# 1_P1.net
KiCad netlist of a schematic drawn in Altium Designer
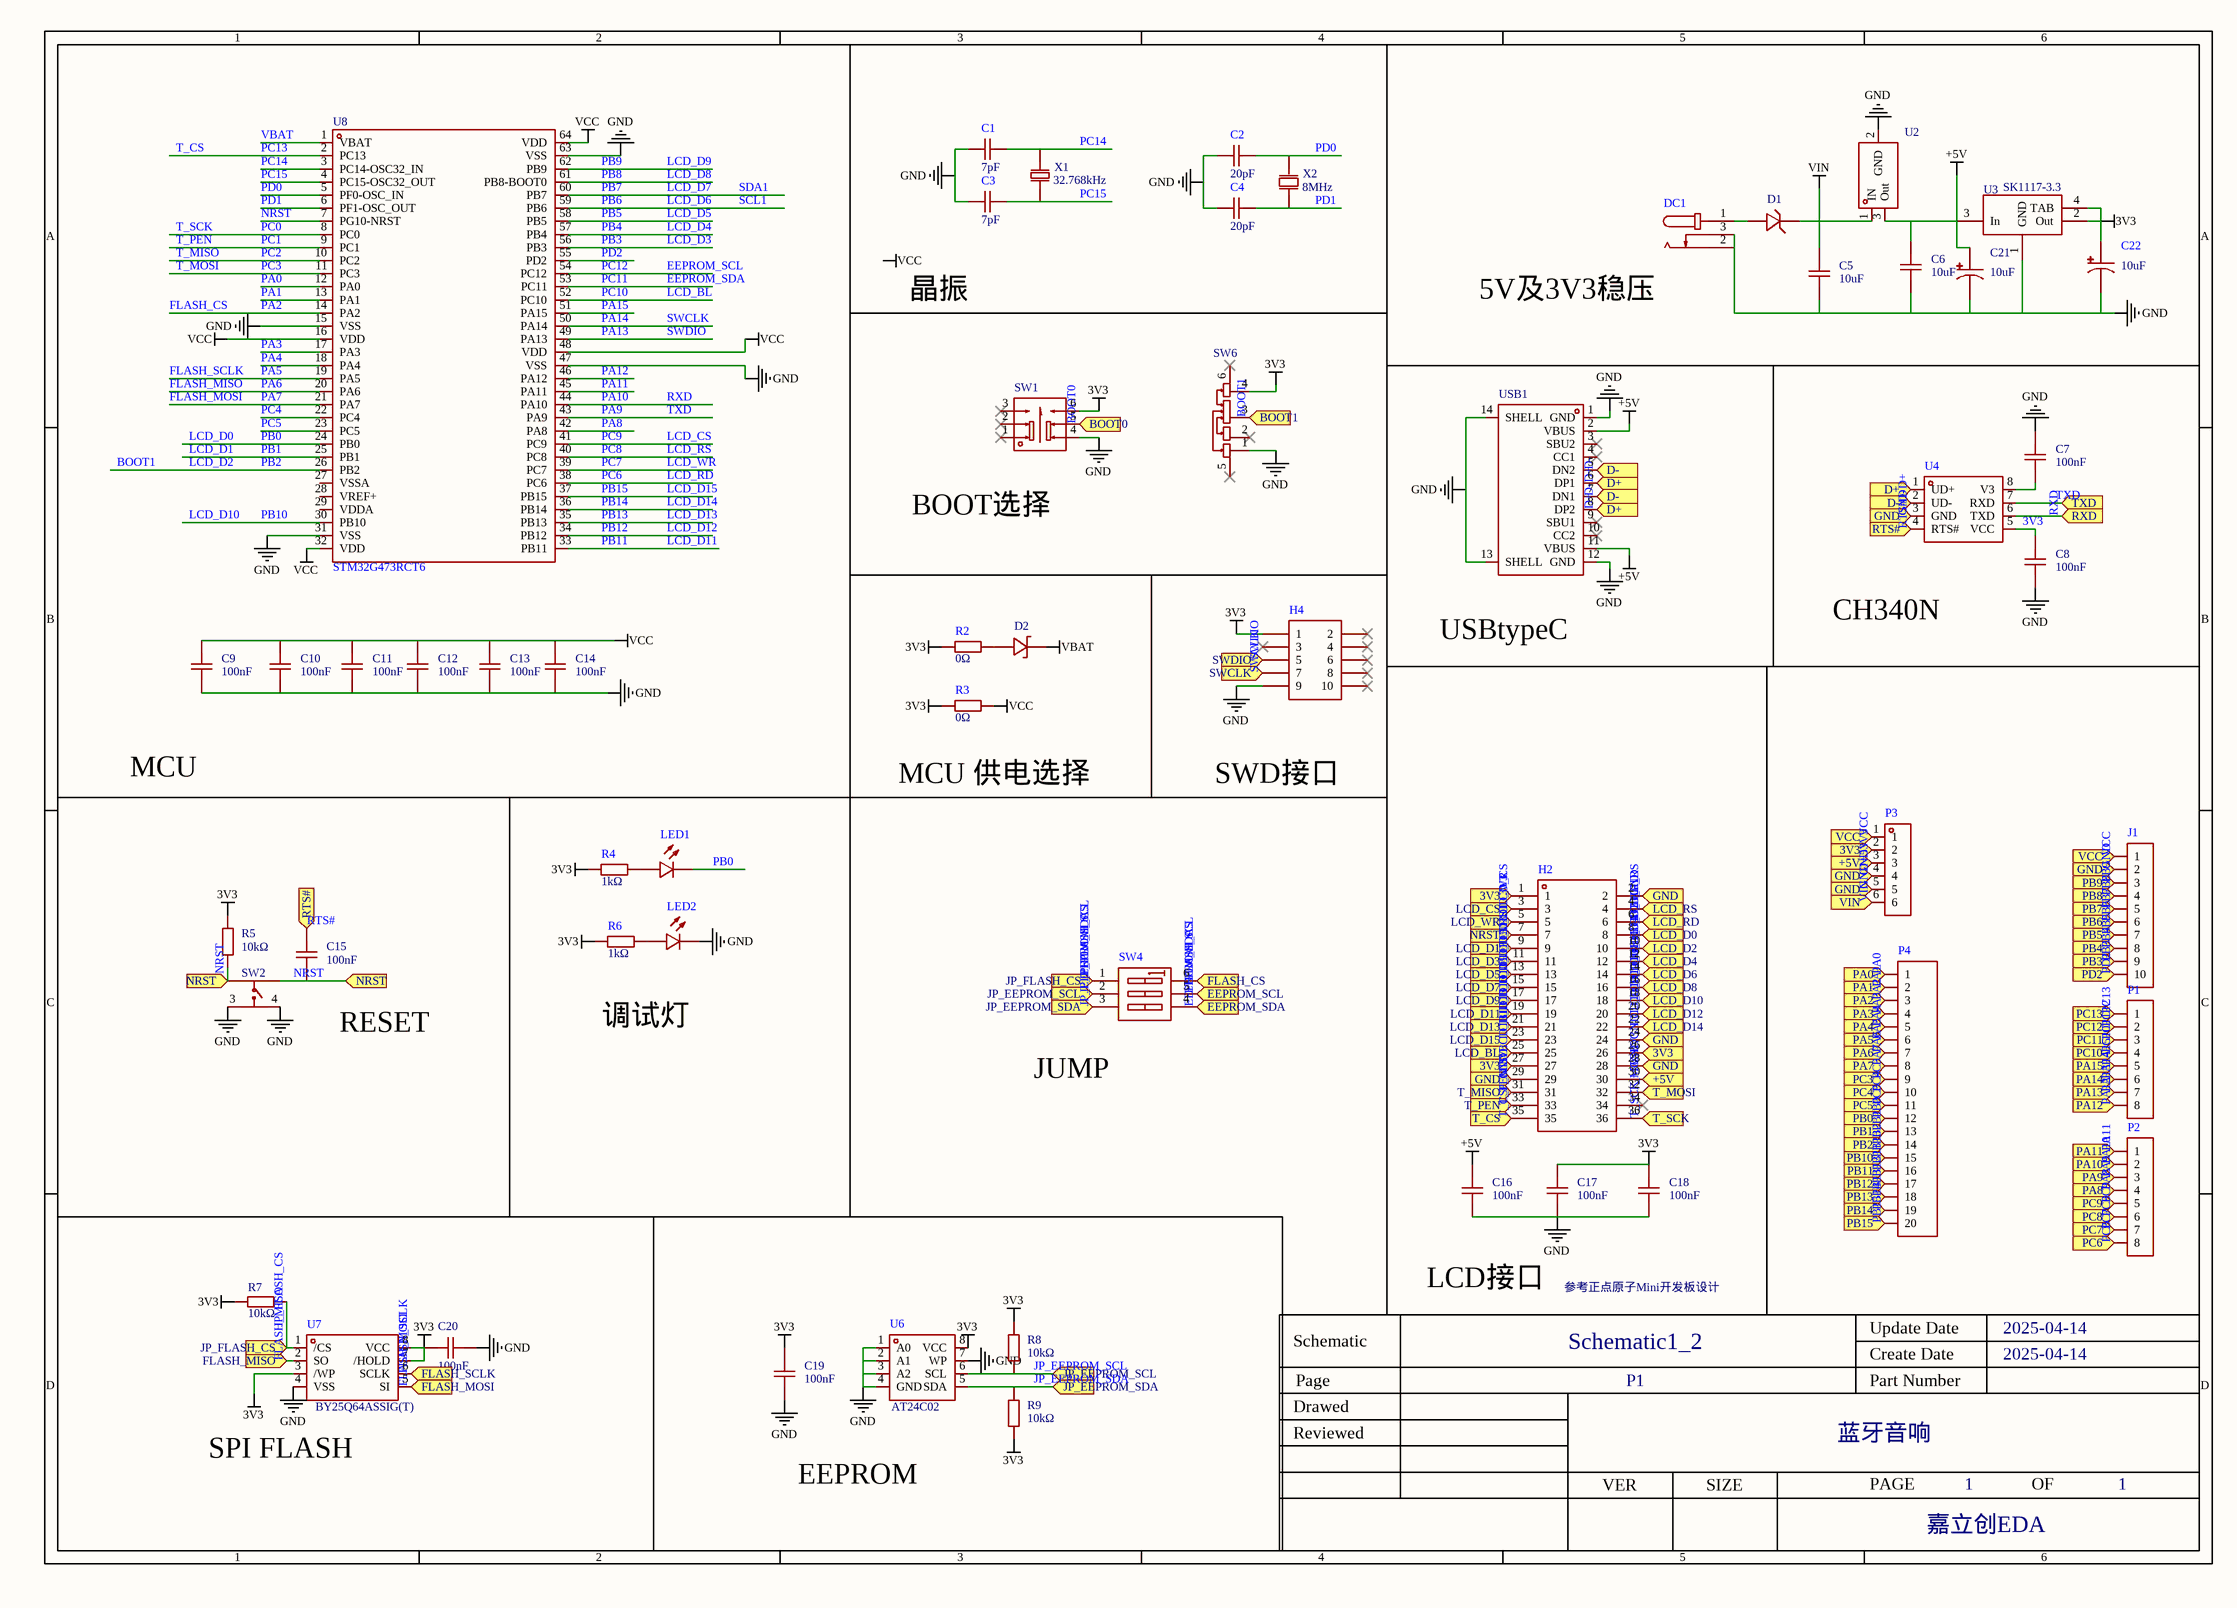
[diagram p0: 1_P1.schdoc]

(export (version "E")
  (design (tool "Eeschema 10.0.6"))
  (components
    (comp (ref "C1")
      (value "7pF")
      (footprint "C0603")
      (fields
        (field (name "MANUFACTURER") "FH(风华)")
        (field (name "MANUFACTURER PART") "0603CG7R0C500NT")
        (field (name "TOLERANCE") "±0.25pF")
        (field (name "ALTIUM_VALUE") "7pF")
      )
      (libsource (lib "altium-import") (part "root_0_0603CG7R0C500NT_"))
    )
    (comp (ref "C2")
      (value "20pF")
      (footprint "C0603")
      (fields
        (field (name "MANUFACTURER") "SAMSUNG(三星)")
        (field (name "MANUFACTURER PART") "CL10C200JB8NNNC")
        (field (name "ALTIUM_VALUE") "20pF")
        (field (name "TOLERANCE") "±5%")
      )
      (libsource (lib "altium-import") (part "root_0_CL10C200JB8NNNC_"))
    )
    (comp (ref "C3")
      (value "7pF")
      (footprint "C0603")
      (fields
        (field (name "MANUFACTURER") "FH(风华)")
        (field (name "MANUFACTURER PART") "0603CG7R0C500NT")
        (field (name "TOLERANCE") "±0.25pF")
        (field (name "ALTIUM_VALUE") "7pF")
      )
      (libsource (lib "altium-import") (part "root_0_0603CG7R0C500NT_"))
    )
    (comp (ref "C4")
      (value "20pF")
      (footprint "C0603")
      (fields
        (field (name "MANUFACTURER") "SAMSUNG(三星)")
        (field (name "MANUFACTURER PART") "CL10C200JB8NNNC")
        (field (name "ALTIUM_VALUE") "20pF")
        (field (name "TOLERANCE") "±5%")
      )
      (libsource (lib "altium-import") (part "root_0_CL10C200JB8NNNC_"))
    )
    (comp (ref "C5")
      (value "10uF")
      (footprint "C0603")
      (fields
        (field (name "MANUFACTURER") "muRata(村田)")
        (field (name "MANUFACTURER PART") "GRM188R6YA106MA73D")
        (field (name "TOLERANCE") "±20%")
      )
      (libsource (lib "altium-import") (part "root_3_GRM188R6YA106MA73D_"))
    )
    (comp (ref "C6")
      (value "10uF")
      (footprint "C0603")
      (fields
        (field (name "MANUFACTURER") "muRata(村田)")
        (field (name "MANUFACTURER PART") "GRM188R6YA106MA73D")
        (field (name "TOLERANCE") "±20%")
      )
      (libsource (lib "altium-import") (part "root_3_GRM188R6YA106MA73D_"))
    )
    (comp (ref "C7")
      (value "100nF")
      (footprint "C0603")
      (fields
        (field (name "MANUFACTURER") "SAMSUNG(三星)")
        (field (name "MANUFACTURER PART") "CL10B104KB8NNNC")
        (field (name "TOLERANCE") "±10%")
      )
      (libsource (lib "altium-import") (part "root_3_CL10B104KB8NNNC_"))
    )
    (comp (ref "C8")
      (value "100nF")
      (footprint "C0603")
      (fields
        (field (name "MANUFACTURER") "SAMSUNG(三星)")
        (field (name "MANUFACTURER PART") "CL10B104KB8NNNC")
        (field (name "TOLERANCE") "±10%")
      )
      (libsource (lib "altium-import") (part "root_3_CL10B104KB8NNNC_"))
    )
    (comp (ref "C9")
      (value "100nF")
      (footprint "C0603")
      (fields
        (field (name "MANUFACTURER") "SAMSUNG(三星)")
        (field (name "MANUFACTURER PART") "CL10B104KB8NNNC")
        (field (name "ALTIUM_VALUE") "100nF")
        (field (name "TOLERANCE") "±10%")
      )
      (libsource (lib "altium-import") (part "root_3_CL10B104KB8NNNC_"))
    )
    (comp (ref "C10")
      (value "100nF")
      (footprint "C0603")
      (fields
        (field (name "MANUFACTURER") "SAMSUNG(三星)")
        (field (name "MANUFACTURER PART") "CL10B104KB8NNNC")
        (field (name "ALTIUM_VALUE") "100nF")
        (field (name "TOLERANCE") "±10%")
      )
      (libsource (lib "altium-import") (part "root_3_CL10B104KB8NNNC_"))
    )
    (comp (ref "C11")
      (value "100nF")
      (footprint "C0603")
      (fields
        (field (name "MANUFACTURER") "SAMSUNG(三星)")
        (field (name "MANUFACTURER PART") "CL10B104KB8NNNC")
        (field (name "ALTIUM_VALUE") "100nF")
        (field (name "TOLERANCE") "±10%")
      )
      (libsource (lib "altium-import") (part "root_3_CL10B104KB8NNNC_"))
    )
    (comp (ref "C12")
      (value "100nF")
      (footprint "C0603")
      (fields
        (field (name "MANUFACTURER") "SAMSUNG(三星)")
        (field (name "MANUFACTURER PART") "CL10B104KB8NNNC")
        (field (name "ALTIUM_VALUE") "100nF")
        (field (name "TOLERANCE") "±10%")
      )
      (libsource (lib "altium-import") (part "root_3_CL10B104KB8NNNC_"))
    )
    (comp (ref "C13")
      (value "100nF")
      (footprint "C0603")
      (fields
        (field (name "MANUFACTURER") "SAMSUNG(三星)")
        (field (name "MANUFACTURER PART") "CL10B104KB8NNNC")
        (field (name "ALTIUM_VALUE") "100nF")
        (field (name "TOLERANCE") "±10%")
      )
      (libsource (lib "altium-import") (part "root_3_CL10B104KB8NNNC_"))
    )
    (comp (ref "C14")
      (value "100nF")
      (footprint "C0603")
      (fields
        (field (name "MANUFACTURER") "SAMSUNG(三星)")
        (field (name "MANUFACTURER PART") "CL10B104KB8NNNC")
        (field (name "ALTIUM_VALUE") "100nF")
        (field (name "TOLERANCE") "±10%")
      )
      (libsource (lib "altium-import") (part "root_3_CL10B104KB8NNNC_"))
    )
    (comp (ref "C15")
      (value "100nF")
      (footprint "C0603")
      (fields
        (field (name "MANUFACTURER") "SAMSUNG(三星)")
        (field (name "MANUFACTURER PART") "CL10B104KB8NNNC")
        (field (name "ALTIUM_VALUE") "100nF")
        (field (name "TOLERANCE") "±10%")
      )
      (libsource (lib "altium-import") (part "root_1_CL10B104KB8NNNC_"))
    )
    (comp (ref "C16")
      (value "100nF")
      (footprint "C0603")
      (fields
        (field (name "MANUFACTURER") "SAMSUNG(三星)")
        (field (name "MANUFACTURER PART") "CL10B104KB8NNNC")
        (field (name "ALTIUM_VALUE") "100nF")
        (field (name "TOLERANCE") "±10%")
      )
      (libsource (lib "altium-import") (part "root_3_CL10B104KB8NNNC_"))
    )
    (comp (ref "C17")
      (value "100nF")
      (footprint "C0603")
      (fields
        (field (name "MANUFACTURER") "SAMSUNG(三星)")
        (field (name "MANUFACTURER PART") "CL10B104KB8NNNC")
        (field (name "ALTIUM_VALUE") "100nF")
        (field (name "TOLERANCE") "±10%")
      )
      (libsource (lib "altium-import") (part "root_3_CL10B104KB8NNNC_"))
    )
    (comp (ref "C18")
      (value "100nF")
      (footprint "C0603")
      (fields
        (field (name "MANUFACTURER") "SAMSUNG(三星)")
        (field (name "MANUFACTURER PART") "CL10B104KB8NNNC")
        (field (name "ALTIUM_VALUE") "100nF")
        (field (name "TOLERANCE") "±10%")
      )
      (libsource (lib "altium-import") (part "root_3_CL10B104KB8NNNC_"))
    )
    (comp (ref "C19")
      (value "100nF")
      (footprint "C0603")
      (fields
        (field (name "MANUFACTURER") "SAMSUNG(三星)")
        (field (name "MANUFACTURER PART") "CL10B104KB8NNNC")
        (field (name "ALTIUM_VALUE") "100nF")
        (field (name "TOLERANCE") "±10%")
      )
      (libsource (lib "altium-import") (part "root_3_CL10B104KB8NNNC_"))
    )
    (comp (ref "C20")
      (value "100nF")
      (footprint "C0603")
      (fields
        (field (name "MANUFACTURER") "SAMSUNG(三星)")
        (field (name "MANUFACTURER PART") "CL10B104KB8NNNC")
        (field (name "ALTIUM_VALUE") "100nF")
        (field (name "TOLERANCE") "±10%")
      )
      (libsource (lib "altium-import") (part "root_0_CL10B104KB8NNNC_"))
    )
    (comp (ref "C21")
      (value "10uF")
      (footprint "CAP-SMD_L3.2-W1.6")
      (fields
        (field (name "MANUFACTURER") "TORCH(火炬)")
        (field (name "MANUFACTURER PART") "CA45-A-10V-10F-K")
        (field (name "ALTIUM_VALUE") "10uF")
        (field (name "TOLERANCE") "±10%")
      )
      (libsource (lib "altium-import") (part "root_3_CA45-A-10V-10μF-K_"))
    )
    (comp (ref "C22")
      (value "10uF")
      (footprint "CAP-SMD_L3.2-W1.6")
      (fields
        (field (name "MANUFACTURER") "TORCH(火炬)")
        (field (name "MANUFACTURER PART") "CA45-A-10V-10F-K")
        (field (name "ALTIUM_VALUE") "10uF")
        (field (name "TOLERANCE") "±10%")
      )
      (libsource (lib "altium-import") (part "root_3_CA45-A-10V-10μF-K_"))
    )
    (comp (ref "D1")
      (value "~")
      (footprint "SMA_L4.3-W2.7-LS5.1-RD")
      (fields (field (name "MANUFACTURER") "UMW(友台半导体)") (field (name "MANUFACTURER PART") "SS34"))
      (libsource (lib "altium-import") (part "root_2_SS34_"))
    )
    (comp (ref "D2")
      (value "1N5819WS")
      (footprint "SOD-323_L1.8-W1.3-LS2.5-RD")
      (fields (field (name "MANUFACTURER") "Hottech(合科泰)"))
      (libsource (lib "altium-import") (part "root_2_1N5819WS_C191023_"))
    )
    (comp (ref "DC1")
      (value "~")
      (footprint "DC-IN-TH_DC-005-20A")
      (fields (field (name "MANUFACTURER") "韩国韩荣") (field (name "MANUFACTURER PART") "DC-005-20A"))
      (libsource (lib "altium-import") (part "root_0_DC-005-20A_"))
    )
    (comp (ref "H2")
      (value "DS1023-2*18SF11")
      (footprint "HDR-TH_36P-P2.54-V-F-R2-C18-S2.54-1")
      (fields (field (name "MANUFACTURER") "CONNFLY"))
      (libsource (lib "altium-import") (part "root_0_DS1023-2*18SF11_"))
    )
    (comp (ref "H4")
      (value "DS1023-2*5SF11")
      (footprint "HDR-TH_10P-P2.54-V-F-R2-C5-S2.54")
      (fields (field (name "MANUFACTURER") "CONNFLY"))
      (libsource (lib "altium-import") (part "root_0_DS1023-2*5SF11_"))
    )
    (comp (ref "J1")
      (value "~")
      (footprint "HDR-TH_10P-P2.54-V-F")
      (fields (field (name "MANUFACTURER") "BOOMELE(博穆精密)") (field (name "MANUFACTURER PART") "2.54-1*10P母"))
      (libsource (lib "altium-import") (part "root_0_2.54-1*10P母_"))
    )
    (comp (ref "LED1")
      (value "19-217/GHC-YR1S2/3T")
      (footprint "LED0603-R-RD")
      (fields (field (name "MANUFACTURER") "EVERLIGHT(台湾亿光)"))
      (libsource (lib "altium-import") (part "root_0_19-217/GHC-YR1S2/3T_"))
    )
    (comp (ref "LED2")
      (value "19-217/GHC-YR1S2/3T")
      (footprint "LED0603-R-RD")
      (fields (field (name "MANUFACTURER") "EVERLIGHT(台湾亿光)"))
      (libsource (lib "altium-import") (part "root_0_19-217/GHC-YR1S2/3T_"))
    )
    (comp (ref "P1")
      (value "~")
      (footprint "HDR-TH_8P-P2.54-V-F-1")
      (fields (field (name "MANUFACTURER") "BOOMELE(博穆精密)") (field (name "MANUFACTURER PART") "2.54-1*8P母环保"))
      (libsource (lib "altium-import") (part "root_0_2.54-1*8P母环保_"))
    )
    (comp (ref "P2")
      (value "~")
      (footprint "HDR-TH_8P-P2.54-V-F-1")
      (fields (field (name "MANUFACTURER") "BOOMELE(博穆精密)") (field (name "MANUFACTURER PART") "2.54-1*8P母环保"))
      (libsource (lib "altium-import") (part "root_0_2.54-1*8P母环保_"))
    )
    (comp (ref "P3")
      (value "~")
      (footprint "HDR-TH_6P-P2.54-V-F")
      (fields (field (name "MANUFACTURER") "BOOMELE(博穆精密)") (field (name "MANUFACTURER PART") "2.54-1*6P母"))
      (libsource (lib "altium-import") (part "root_0_2.54-1*6P母_"))
    )
    (comp (ref "P4")
      (value "2.54-1*20P母")
      (footprint "HDR-TH_20P-P2.54-V-F")
      (fields (field (name "MANUFACTURER") "BOOMELE(博穆精密)"))
      (libsource (lib "altium-import") (part "root_0_2.54-1*20P母_"))
    )
    (comp (ref "R2")
      (value "0Ω")
      (footprint "R0603")
      (fields
        (field (name "MANUFACTURER") "UNI-ROYAL(厚声)")
        (field (name "MANUFACTURER PART") "0603WAF0000T5E")
        (field (name "TOLERANCE") "±1%")
        (field (name "ALTIUM_VALUE") "0Ω")
      )
      (libsource (lib "altium-import") (part "root_0_0603WAF0000T5E_"))
    )
    (comp (ref "R3")
      (value "0Ω")
      (footprint "R0603")
      (fields
        (field (name "MANUFACTURER") "UNI-ROYAL(厚声)")
        (field (name "MANUFACTURER PART") "0603WAF0000T5E")
        (field (name "TOLERANCE") "±1%")
        (field (name "ALTIUM_VALUE") "0Ω")
      )
      (libsource (lib "altium-import") (part "root_0_0603WAF0000T5E_"))
    )
    (comp (ref "R4")
      (value "1kΩ")
      (footprint "R0603")
      (fields
        (field (name "MANUFACTURER") "UNI-ROYAL(厚声)")
        (field (name "MANUFACTURER PART") "0603WAF1001T5E")
        (field (name "TOLERANCE") "±1%")
      )
      (libsource (lib "altium-import") (part "root_0_0603WAF1001T5E_"))
    )
    (comp (ref "R5")
      (value "10kΩ")
      (footprint "R0603")
      (fields
        (field (name "MANUFACTURER") "UNI-ROYAL(厚声)")
        (field (name "MANUFACTURER PART") "0603WAF1002T5E")
        (field (name "TOLERANCE") "±1%")
      )
      (libsource (lib "altium-import") (part "root_1_0603WAF1002T5E_"))
    )
    (comp (ref "R6")
      (value "1kΩ")
      (footprint "R0603")
      (fields
        (field (name "MANUFACTURER") "UNI-ROYAL(厚声)")
        (field (name "MANUFACTURER PART") "0603WAF1001T5E")
        (field (name "TOLERANCE") "±1%")
      )
      (libsource (lib "altium-import") (part "root_0_0603WAF1001T5E_"))
    )
    (comp (ref "R7")
      (value "10kΩ")
      (footprint "R0603")
      (fields
        (field (name "MANUFACTURER") "UNI-ROYAL(厚声)")
        (field (name "MANUFACTURER PART") "0603WAF1002T5E")
        (field (name "TOLERANCE") "±1%")
      )
      (libsource (lib "altium-import") (part "root_2_0603WAF1002T5E_"))
    )
    (comp (ref "R8")
      (value "10kΩ")
      (footprint "R0603")
      (fields
        (field (name "MANUFACTURER") "UNI-ROYAL(厚声)")
        (field (name "MANUFACTURER PART") "0603WAF1002T5E")
        (field (name "TOLERANCE") "±1%")
      )
      (libsource (lib "altium-import") (part "root_1_0603WAF1002T5E_"))
    )
    (comp (ref "R9")
      (value "10kΩ")
      (footprint "R0603")
      (fields
        (field (name "MANUFACTURER") "UNI-ROYAL(厚声)")
        (field (name "MANUFACTURER PART") "0603WAF1002T5E")
        (field (name "TOLERANCE") "±1%")
      )
      (libsource (lib "altium-import") (part "root_1_0603WAF1002T5E_"))
    )
    (comp (ref "SW1")
      (value "XKB5858-Z-75")
      (footprint "SW-TH_6P-L5.8-W5.8-P2.00-LS4.5-BL")
      (fields (field (name "MANUFACTURER") "XKB Connectivity(中国星坤)"))
      (libsource (lib "altium-import") (part "root_3_XKB5858-Z-75_"))
    )
    (comp (ref "SW2")
      (value "~")
      (footprint "SW-SMD_4P-L4.5-W4.5-P3.00-LS6.8")
      (fields
        (field (name "MANUFACTURER") "BOOMELE(博穆精密)")
        (field (name "MANUFACTURER PART") "4.5x4.5x3.8贴片")
      )
      (libsource (lib "altium-import") (part "root_0_4.5x4.5x3.8贴片_"))
    )
    (comp (ref "SW4")
      (value "DSHP03TS-S")
      (footprint "SW-SMD_DSHP03TS-S")
      (fields (field (name "MANUFACTURER") "XKB Connectivity(中国星坤)"))
      (libsource (lib "altium-import") (part "root_0_DSHP03TS-S_"))
    )
    (comp (ref "SW6")
      (value "K3-1311S-F1")
      (footprint "SW-SMD_K3-1311S-F1")
      (fields (field (name "MANUFACTURER") "韩国韩荣"))
      (libsource (lib "altium-import") (part "root_1_K3-1311S-F1_"))
    )
    (comp (ref "U2")
      (value "~")
      (footprint "TO-252-2_L6.6-W6.1-P4.58-LS10.1-BR-CW")
      (fields (field (name "MANUFACTURER") "CJ（江苏长电/长晶）") (field (name "MANUFACTURER PART") "CJ7805 3%"))
      (libsource (lib "altium-import") (part "root_1_CJ7805 3%_"))
    )
    (comp (ref "U3")
      (value "~")
      (footprint "SOT-223_L6.5-W3.5-P2.30-LS7.0-BR")
      (fields
        (field (name "DEVICE") "SK1117-3.3")
        (field (name "MANUFACTURER") "SHIKUES(时科)")
        (field (name "MANUFACTURER PART") "SK1117-3.3")
      )
      (libsource (lib "altium-import") (part "root_0_SK1117-3.3_"))
    )
    (comp (ref "U4")
      (value "~")
      (footprint "SOP-8_L4.9-W3.9-P1.27-LS6.0-BL")
      (fields (field (name "MANUFACTURER") "WCH(南京沁恒)") (field (name "MANUFACTURER PART") "CH340N"))
      (libsource (lib "altium-import") (part "root_0_CH340N_"))
    )
    (comp (ref "U6")
      (value "AT24C02")
      (footprint "SOP-8_L5.0-W4.0-P1.27-LS6.0-BL")
      (fields (field (name "DEVICE") "AT24C02") (field (name "MANUFACTURER") "IDCHIP(英锐芯)"))
      (libsource (lib "altium-import") (part "root_0_AT24C02_"))
    )
    (comp (ref "U7")
      (value "BY25Q64ASSIG(T)")
      (footprint "SOIC-8_L5.3-W5.3-P1.27-LS8.0-BL")
      (fields (field (name "DEVICE") "BY25Q64ASSIG(T)") (field (name "MANUFACTURER") "BOYAMICRO(博雅)"))
      (libsource (lib "altium-import") (part "root_0_BY25Q64ASSIG(T)_"))
    )
    (comp (ref "U8")
      (value "STM32G473RCT6")
      (footprint "LQFP-64_L10.0-W10.0-P0.50-LS12.0-BL")
      (fields (field (name "MANUFACTURER") "ST(意法半导体)"))
      (libsource (lib "altium-import") (part "root_0_STM32G473RCT6_"))
    )
    (comp (ref "USB1")
      (value "~")
      (footprint "USB-C-SMD_TYPE-C-6PIN-2MD-073")
      (fields
        (field (name "MANUFACTURER") "SHOU HAN(首韩)")
        (field (name "MANUFACTURER PART") "TYPE-C 16PIN 2MD(073)")
      )
      (libsource (lib "altium-import") (part "root_0_mirrored_TYPE-C 16PIN 2MD(073)_"))
    )
    (comp (ref "X1")
      (value "32.768kHz")
      (footprint "FC-135R_L3.2-W1.5")
      (fields
        (field (name "MANUFACTURER") "EPSON(爱普生)")
        (field (name "MANUFACTURER PART") "Q13FC1350000200")
        (field (name "ALTIUM_VALUE") "32.768kHz")
      )
      (libsource (lib "altium-import") (part "root_3_Q13FC1350000200_"))
    )
    (comp (ref "X2")
      (value "8MHz")
      (footprint "CRYSTAL-SMD_L5.0-W3.2")
      (fields
        (field (name "MANUFACTURER") "YXC扬兴科技")
        (field (name "MANUFACTURER PART") "X50328MSB2GI")
        (field (name "ALTIUM_VALUE") "8MHz")
      )
      (libsource (lib "altium-import") (part "root_1_X50328MSB2GI_"))
    )
  )
  (nets
    (net (code "1") (name "+5V") (class "Default")
      (node (ref "C16") (pin "1") (pinfunction "1_1") (pintype "passive"))
      (node (ref "C21") (pin "1") (pinfunction "1_1") (pintype "passive"))
      (node (ref "C6") (pin "1") (pinfunction "1_1") (pintype "passive"))
      (node (ref "H2") (pin "30") (pinfunction "30_30") (pintype "passive"))
      (node (ref "P3") (pin "3") (pinfunction "3_3") (pintype "passive"))
      (node (ref "U2") (pin "3") (pinfunction "Out_3") (pintype "passive"))
      (node (ref "U3") (pin "3") (pinfunction "In_3") (pintype "passive"))
      (node (ref "USB1") (pin "11") (pinfunction "VBUS_11") (pintype "passive"))
      (node (ref "USB1") (pin "2") (pinfunction "VBUS_2") (pintype "passive"))
    )
    (net (code "2") (name "/BOOT0") (class "Default")
      (node (ref "SW1") (pin "5") (pinfunction "5_5") (pintype "passive"))
    )
    (net (code "3") (name "/BOOT1") (class "Default")
      (node (ref "H2") (pin "10") (pinfunction "10_10") (pintype "passive"))
      (node (ref "P4") (pin "14") (pinfunction "14_14") (pintype "passive"))
      (node (ref "SW6") (pin "3") (pinfunction "3_3") (pintype "passive"))
      (node (ref "U8") (pin "26") (pinfunction "PB2_26") (pintype "passive"))
    )
    (net (code "4") (name "/D+") (class "Default")
      (node (ref "U4") (pin "1") (pinfunction "UD+_1") (pintype "passive"))
      (node (ref "USB1") (pin "6") (pinfunction "DP1_6") (pintype "passive"))
      (node (ref "USB1") (pin "8") (pinfunction "DP2_8") (pintype "passive"))
    )
    (net (code "5") (name "/D-") (class "Default")
      (node (ref "U4") (pin "2") (pinfunction "UD-_2") (pintype "passive"))
      (node (ref "USB1") (pin "5") (pinfunction "DN2_5") (pintype "passive"))
      (node (ref "USB1") (pin "7") (pinfunction "DN1_7") (pintype "passive"))
    )
    (net (code "6") (name "/EEPROM_SCL") (class "Default")
      (node (ref "P1") (pin "2") (pinfunction "2_2") (pintype "passive"))
      (node (ref "SW4") (pin "5") (pinfunction "5_5") (pintype "passive"))
      (node (ref "U8") (pin "54") (pinfunction "PC12_54") (pintype "passive"))
    )
    (net (code "7") (name "/EEPROM_SDA") (class "Default")
      (node (ref "P1") (pin "3") (pinfunction "3_3") (pintype "passive"))
      (node (ref "SW4") (pin "4") (pinfunction "4_4") (pintype "passive"))
      (node (ref "U8") (pin "53") (pinfunction "PC11_53") (pintype "passive"))
    )
    (net (code "8") (name "/FLASH_CS") (class "Default")
      (node (ref "P4") (pin "3") (pinfunction "3_3") (pintype "passive"))
      (node (ref "SW4") (pin "6") (pinfunction "6_6") (pintype "passive"))
      (node (ref "U8") (pin "14") (pinfunction "PA2_14") (pintype "passive"))
    )
    (net (code "9") (name "/FLASH_MISO") (class "Default")
      (node (ref "P4") (pin "7") (pinfunction "7_7") (pintype "passive"))
      (node (ref "U7") (pin "2") (pinfunction "SO_2") (pintype "passive"))
      (node (ref "U8") (pin "20") (pinfunction "PA6_20") (pintype "passive"))
    )
    (net (code "10") (name "/FLASH_MOSI") (class "Default")
      (node (ref "P4") (pin "8") (pinfunction "8_8") (pintype "passive"))
      (node (ref "U7") (pin "5") (pinfunction "SI_5") (pintype "passive"))
      (node (ref "U8") (pin "21") (pinfunction "PA7_21") (pintype "passive"))
    )
    (net (code "11") (name "/FLASH_SCLK") (class "Default")
      (node (ref "P4") (pin "6") (pinfunction "6_6") (pintype "passive"))
      (node (ref "U7") (pin "6") (pinfunction "SCLK_6") (pintype "passive"))
      (node (ref "U8") (pin "19") (pinfunction "PA5_19") (pintype "passive"))
    )
    (net (code "12") (name "/JP_EEPROM_SCL") (class "Default")
      (node (ref "R8") (pin "1") (pinfunction "1_1") (pintype "passive"))
      (node (ref "SW4") (pin "2") (pinfunction "2_2") (pintype "passive"))
      (node (ref "U6") (pin "6") (pinfunction "SCL_6") (pintype "passive"))
    )
    (net (code "13") (name "/JP_EEPROM_SDA") (class "Default")
      (node (ref "R9") (pin "2") (pinfunction "2_2") (pintype "passive"))
      (node (ref "SW4") (pin "3") (pinfunction "3_3") (pintype "passive"))
      (node (ref "U6") (pin "5") (pinfunction "SDA_5") (pintype "passive"))
    )
    (net (code "14") (name "/JP_FLASH_CS") (class "Default")
      (node (ref "R7") (pin "1") (pinfunction "1_1") (pintype "passive"))
      (node (ref "SW4") (pin "1") (pinfunction "1_1") (pintype "passive"))
      (node (ref "U7") (pin "1") (pinfunction "/CS_1") (pintype "passive"))
    )
    (net (code "15") (name "/LCD_BL") (class "Default")
      (node (ref "H2") (pin "25") (pinfunction "25_25") (pintype "passive"))
      (node (ref "P1") (pin "4") (pinfunction "4_4") (pintype "passive"))
      (node (ref "U8") (pin "52") (pinfunction "PC10_52") (pintype "passive"))
    )
    (net (code "16") (name "/LCD_CS") (class "Default")
      (node (ref "H2") (pin "3") (pinfunction "3_3") (pintype "passive"))
      (node (ref "P2") (pin "5") (pinfunction "5_5") (pintype "passive"))
      (node (ref "U8") (pin "41") (pinfunction "PC9_41") (pintype "passive"))
    )
    (net (code "17") (name "/LCD_D0") (class "Default")
      (node (ref "H2") (pin "8") (pinfunction "8_8") (pintype "passive"))
      (node (ref "LED1") (pin "2") (pinfunction "C_2") (pintype "passive"))
      (node (ref "P4") (pin "12") (pinfunction "12_12") (pintype "passive"))
      (node (ref "U8") (pin "24") (pinfunction "PB0_24") (pintype "passive"))
    )
    (net (code "18") (name "/LCD_D1") (class "Default")
      (node (ref "H2") (pin "9") (pinfunction "9_9") (pintype "passive"))
      (node (ref "P4") (pin "13") (pinfunction "13_13") (pintype "passive"))
      (node (ref "U8") (pin "25") (pinfunction "PB1_25") (pintype "passive"))
    )
    (net (code "19") (name "/LCD_D3") (class "Default")
      (node (ref "H2") (pin "11") (pinfunction "11_11") (pintype "passive"))
      (node (ref "J1") (pin "9") (pinfunction "9_9") (pintype "passive"))
      (node (ref "U8") (pin "56") (pinfunction "PB3_56") (pintype "passive"))
    )
    (net (code "20") (name "/LCD_D4") (class "Default")
      (node (ref "H2") (pin "12") (pinfunction "12_12") (pintype "passive"))
      (node (ref "J1") (pin "8") (pinfunction "8_8") (pintype "passive"))
      (node (ref "U8") (pin "57") (pinfunction "PB4_57") (pintype "passive"))
    )
    (net (code "21") (name "/LCD_D5") (class "Default")
      (node (ref "H2") (pin "13") (pinfunction "13_13") (pintype "passive"))
      (node (ref "J1") (pin "7") (pinfunction "7_7") (pintype "passive"))
      (node (ref "U8") (pin "58") (pinfunction "PB5_58") (pintype "passive"))
    )
    (net (code "22") (name "/LCD_D6") (class "Default")
      (node (ref "H2") (pin "14") (pinfunction "14_14") (pintype "passive"))
      (node (ref "J1") (pin "6") (pinfunction "6_6") (pintype "passive"))
      (node (ref "U8") (pin "59") (pinfunction "PB6_59") (pintype "passive"))
    )
    (net (code "23") (name "/LCD_D7") (class "Default")
      (node (ref "H2") (pin "15") (pinfunction "15_15") (pintype "passive"))
      (node (ref "J1") (pin "5") (pinfunction "5_5") (pintype "passive"))
      (node (ref "U8") (pin "60") (pinfunction "PB7_60") (pintype "passive"))
    )
    (net (code "24") (name "/LCD_D8") (class "Default")
      (node (ref "H2") (pin "16") (pinfunction "16_16") (pintype "passive"))
      (node (ref "J1") (pin "4") (pinfunction "4_4") (pintype "passive"))
      (node (ref "U8") (pin "61") (pinfunction "PB8-BOOT0_61") (pintype "passive"))
    )
    (net (code "25") (name "/LCD_D9") (class "Default")
      (node (ref "H2") (pin "17") (pinfunction "17_17") (pintype "passive"))
      (node (ref "J1") (pin "3") (pinfunction "3_3") (pintype "passive"))
      (node (ref "U8") (pin "62") (pinfunction "PB9_62") (pintype "passive"))
    )
    (net (code "26") (name "/LCD_D10") (class "Default")
      (node (ref "H2") (pin "18") (pinfunction "18_18") (pintype "passive"))
      (node (ref "P4") (pin "15") (pinfunction "15_15") (pintype "passive"))
      (node (ref "U8") (pin "30") (pinfunction "PB10_30") (pintype "passive"))
    )
    (net (code "27") (name "/LCD_D11") (class "Default")
      (node (ref "H2") (pin "19") (pinfunction "19_19") (pintype "passive"))
      (node (ref "P4") (pin "16") (pinfunction "16_16") (pintype "passive"))
      (node (ref "U8") (pin "33") (pinfunction "PB11_33") (pintype "passive"))
    )
    (net (code "28") (name "/LCD_D12") (class "Default")
      (node (ref "H2") (pin "20") (pinfunction "20_20") (pintype "passive"))
      (node (ref "P4") (pin "17") (pinfunction "17_17") (pintype "passive"))
      (node (ref "U8") (pin "34") (pinfunction "PB12_34") (pintype "passive"))
    )
    (net (code "29") (name "/LCD_D13") (class "Default")
      (node (ref "H2") (pin "21") (pinfunction "21_21") (pintype "passive"))
      (node (ref "P4") (pin "18") (pinfunction "18_18") (pintype "passive"))
      (node (ref "U8") (pin "35") (pinfunction "PB13_35") (pintype "passive"))
    )
    (net (code "30") (name "/LCD_D14") (class "Default")
      (node (ref "H2") (pin "22") (pinfunction "22_22") (pintype "passive"))
      (node (ref "P4") (pin "19") (pinfunction "19_19") (pintype "passive"))
      (node (ref "U8") (pin "36") (pinfunction "PB14_36") (pintype "passive"))
    )
    (net (code "31") (name "/LCD_D15") (class "Default")
      (node (ref "H2") (pin "23") (pinfunction "23_23") (pintype "passive"))
      (node (ref "P4") (pin "20") (pinfunction "20_20") (pintype "passive"))
      (node (ref "U8") (pin "37") (pinfunction "PB15_37") (pintype "passive"))
    )
    (net (code "32") (name "/LCD_RD") (class "Default")
      (node (ref "H2") (pin "6") (pinfunction "6_6") (pintype "passive"))
      (node (ref "P2") (pin "8") (pinfunction "8_8") (pintype "passive"))
      (node (ref "U8") (pin "38") (pinfunction "PC6_38") (pintype "passive"))
    )
    (net (code "33") (name "/LCD_RS") (class "Default")
      (node (ref "H2") (pin "4") (pinfunction "4_4") (pintype "passive"))
      (node (ref "P2") (pin "6") (pinfunction "6_6") (pintype "passive"))
      (node (ref "U8") (pin "40") (pinfunction "PC8_40") (pintype "passive"))
    )
    (net (code "34") (name "/LCD_WR") (class "Default")
      (node (ref "H2") (pin "5") (pinfunction "5_5") (pintype "passive"))
      (node (ref "P2") (pin "7") (pinfunction "7_7") (pintype "passive"))
      (node (ref "U8") (pin "39") (pinfunction "PC7_39") (pintype "passive"))
    )
    (net (code "35") (name "/NRST") (class "Default")
      (node (ref "C15") (pin "1") (pinfunction "1_1") (pintype "passive"))
      (node (ref "H2") (pin "7") (pinfunction "7_7") (pintype "passive"))
      (node (ref "R5") (pin "1") (pinfunction "1_1") (pintype "passive"))
      (node (ref "SW2") (pin "1") (pinfunction "2_1") (pintype "passive"))
      (node (ref "SW2") (pin "2") (pinfunction "1_2") (pintype "passive"))
      (node (ref "U8") (pin "7") (pinfunction "PG10-NRST_7") (pintype "passive"))
    )
    (net (code "36") (name "/PA0") (class "Default")
      (node (ref "P4") (pin "1") (pinfunction "1_1") (pintype "passive"))
      (node (ref "U8") (pin "12") (pinfunction "PA0_12") (pintype "passive"))
    )
    (net (code "37") (name "/PA1") (class "Default")
      (node (ref "P4") (pin "2") (pinfunction "2_2") (pintype "passive"))
      (node (ref "U8") (pin "13") (pinfunction "PA1_13") (pintype "passive"))
    )
    (net (code "38") (name "/PA3") (class "Default")
      (node (ref "P4") (pin "4") (pinfunction "4_4") (pintype "passive"))
      (node (ref "U8") (pin "17") (pinfunction "PA3_17") (pintype "passive"))
    )
    (net (code "39") (name "/PA4") (class "Default")
      (node (ref "P4") (pin "5") (pinfunction "5_5") (pintype "passive"))
      (node (ref "U8") (pin "18") (pinfunction "PA4_18") (pintype "passive"))
    )
    (net (code "40") (name "/PA8") (class "Default")
      (node (ref "P2") (pin "4") (pinfunction "4_4") (pintype "passive"))
      (node (ref "U8") (pin "42") (pinfunction "PA8_42") (pintype "passive"))
    )
    (net (code "41") (name "/PA9") (class "Default")
      (node (ref "P2") (pin "3") (pinfunction "3_3") (pintype "passive"))
      (node (ref "U4") (pin "7") (pinfunction "RXD_7") (pintype "passive"))
      (node (ref "U8") (pin "43") (pinfunction "PA9_43") (pintype "passive"))
    )
    (net (code "42") (name "/PA10") (class "Default")
      (node (ref "P2") (pin "2") (pinfunction "2_2") (pintype "passive"))
      (node (ref "U4") (pin "6") (pinfunction "TXD_6") (pintype "passive"))
      (node (ref "U8") (pin "44") (pinfunction "PA10_44") (pintype "passive"))
    )
    (net (code "43") (name "/PA11") (class "Default")
      (node (ref "P2") (pin "1") (pinfunction "1_1") (pintype "passive"))
      (node (ref "U8") (pin "45") (pinfunction "PA11_45") (pintype "passive"))
    )
    (net (code "44") (name "/PA12") (class "Default")
      (node (ref "P1") (pin "8") (pinfunction "8_8") (pintype "passive"))
      (node (ref "U8") (pin "46") (pinfunction "PA12_46") (pintype "passive"))
    )
    (net (code "45") (name "/PA13") (class "Default")
      (node (ref "H4") (pin "5") (pinfunction "5_5") (pintype "passive"))
      (node (ref "P1") (pin "7") (pinfunction "7_7") (pintype "passive"))
      (node (ref "U8") (pin "49") (pinfunction "PA13_49") (pintype "passive"))
    )
    (net (code "46") (name "/PA14") (class "Default")
      (node (ref "H4") (pin "7") (pinfunction "7_7") (pintype "passive"))
      (node (ref "P1") (pin "6") (pinfunction "6_6") (pintype "passive"))
      (node (ref "U8") (pin "50") (pinfunction "PA14_50") (pintype "passive"))
    )
    (net (code "47") (name "/PA15") (class "Default")
      (node (ref "P1") (pin "5") (pinfunction "5_5") (pintype "passive"))
      (node (ref "U8") (pin "51") (pinfunction "PA15_51") (pintype "passive"))
    )
    (net (code "48") (name "/PC0") (class "Default")
      (node (ref "H2") (pin "36") (pinfunction "36_36") (pintype "passive"))
      (node (ref "U8") (pin "8") (pinfunction "PC0_8") (pintype "passive"))
    )
    (net (code "49") (name "/PC1") (class "Default")
      (node (ref "H2") (pin "33") (pinfunction "33_33") (pintype "passive"))
      (node (ref "U8") (pin "9") (pinfunction "PC1_9") (pintype "passive"))
    )
    (net (code "50") (name "/PC2") (class "Default")
      (node (ref "H2") (pin "31") (pinfunction "31_31") (pintype "passive"))
      (node (ref "U8") (pin "10") (pinfunction "PC2_10") (pintype "passive"))
    )
    (net (code "51") (name "/PC3") (class "Default")
      (node (ref "H2") (pin "32") (pinfunction "32_32") (pintype "passive"))
      (node (ref "P4") (pin "9") (pinfunction "9_9") (pintype "passive"))
      (node (ref "U8") (pin "11") (pinfunction "PC3_11") (pintype "passive"))
    )
    (net (code "52") (name "/PC4") (class "Default")
      (node (ref "P4") (pin "10") (pinfunction "10_10") (pintype "passive"))
      (node (ref "U8") (pin "22") (pinfunction "PC4_22") (pintype "passive"))
    )
    (net (code "53") (name "/PC5") (class "Default")
      (node (ref "P4") (pin "11") (pinfunction "11_11") (pintype "passive"))
      (node (ref "U8") (pin "23") (pinfunction "PC5_23") (pintype "passive"))
    )
    (net (code "54") (name "/PC13") (class "Default")
      (node (ref "H2") (pin "35") (pinfunction "35_35") (pintype "passive"))
      (node (ref "P1") (pin "1") (pinfunction "1_1") (pintype "passive"))
      (node (ref "U8") (pin "2") (pinfunction "PC13_2") (pintype "passive"))
    )
    (net (code "55") (name "/PC14") (class "Default")
      (node (ref "C1") (pin "2") (pinfunction "2_2") (pintype "passive"))
      (node (ref "U8") (pin "3") (pinfunction "PC14-OSC32_IN_3") (pintype "passive"))
      (node (ref "X1") (pin "1") (pinfunction "1_1") (pintype "passive"))
    )
    (net (code "56") (name "/PC15") (class "Default")
      (node (ref "C3") (pin "2") (pinfunction "2_2") (pintype "passive"))
      (node (ref "U8") (pin "4") (pinfunction "PC15-OSC32_OUT_4") (pintype "passive"))
      (node (ref "X1") (pin "2") (pinfunction "2_2") (pintype "passive"))
    )
    (net (code "57") (name "/PD0") (class "Default")
      (node (ref "C2") (pin "2") (pinfunction "2_2") (pintype "passive"))
      (node (ref "U8") (pin "5") (pinfunction "PF0-OSC_IN_5") (pintype "passive"))
      (node (ref "X2") (pin "2") (pinfunction "OSC2_2") (pintype "passive"))
    )
    (net (code "58") (name "/PD1") (class "Default")
      (node (ref "C4") (pin "2") (pinfunction "2_2") (pintype "passive"))
      (node (ref "U8") (pin "6") (pinfunction "PF1-OSC_OUT_6") (pintype "passive"))
      (node (ref "X2") (pin "1") (pinfunction "OSC1_1") (pintype "passive"))
    )
    (net (code "59") (name "/PD2") (class "Default")
      (node (ref "J1") (pin "10") (pinfunction "10_10") (pintype "passive"))
      (node (ref "U8") (pin "55") (pinfunction "PD2_55") (pintype "passive"))
    )
    (net (code "60") (name "/RTS#") (class "Default")
      (node (ref "C15") (pin "2") (pinfunction "2_2") (pintype "passive"))
      (node (ref "U4") (pin "4") (pinfunction "RTS#_4") (pintype "passive"))
    )
    (net (code "61") (name "3V3") (class "Default")
      (node (ref "C17") (pin "1") (pinfunction "1_1") (pintype "passive"))
      (node (ref "C18") (pin "1") (pinfunction "1_1") (pintype "passive"))
      (node (ref "C19") (pin "1") (pinfunction "1_1") (pintype "passive"))
      (node (ref "C20") (pin "1") (pinfunction "1_1") (pintype "passive"))
      (node (ref "C22") (pin "1") (pinfunction "1_1") (pintype "passive"))
      (node (ref "C8") (pin "1") (pinfunction "1_1") (pintype "passive"))
      (node (ref "H2") (pin "1") (pinfunction "1_1") (pintype "passive"))
      (node (ref "H2") (pin "26") (pinfunction "26_26") (pintype "passive"))
      (node (ref "H2") (pin "27") (pinfunction "27_27") (pintype "passive"))
      (node (ref "H4") (pin "1") (pinfunction "1_1") (pintype "passive"))
      (node (ref "P3") (pin "2") (pinfunction "2_2") (pintype "passive"))
      (node (ref "R2") (pin "1") (pinfunction "1_1") (pintype "passive"))
      (node (ref "R3") (pin "1") (pinfunction "1_1") (pintype "passive"))
      (node (ref "R4") (pin "1") (pinfunction "1_1") (pintype "passive"))
      (node (ref "R5") (pin "2") (pinfunction "2_2") (pintype "passive"))
      (node (ref "R6") (pin "1") (pinfunction "1_1") (pintype "passive"))
      (node (ref "R7") (pin "2") (pinfunction "2_2") (pintype "passive"))
      (node (ref "R8") (pin "2") (pinfunction "2_2") (pintype "passive"))
      (node (ref "R9") (pin "1") (pinfunction "1_1") (pintype "passive"))
      (node (ref "SW1") (pin "6") (pinfunction "6_6") (pintype "passive"))
      (node (ref "SW6") (pin "4") (pinfunction "4_4") (pintype "passive"))
      (node (ref "U3") (pin "2") (pinfunction "Out_2") (pintype "passive"))
      (node (ref "U3") (pin "4") (pinfunction "TAB_4") (pintype "passive"))
      (node (ref "U4") (pin "5") (pinfunction "VCC_5") (pintype "passive"))
      (node (ref "U6") (pin "8") (pinfunction "VCC_8") (pintype "passive"))
      (node (ref "U7") (pin "3") (pinfunction "/WP_3") (pintype "passive"))
      (node (ref "U7") (pin "7") (pinfunction "/HOLD_7") (pintype "passive"))
      (node (ref "U7") (pin "8") (pinfunction "VCC_8") (pintype "passive"))
    )
    (net (code "62") (name "GND") (class "Default")
      (node (ref "C1") (pin "1") (pinfunction "1_1") (pintype "passive"))
      (node (ref "C10") (pin "2") (pinfunction "2_2") (pintype "passive"))
      (node (ref "C11") (pin "2") (pinfunction "2_2") (pintype "passive"))
      (node (ref "C12") (pin "2") (pinfunction "2_2") (pintype "passive"))
      (node (ref "C13") (pin "2") (pinfunction "2_2") (pintype "passive"))
      (node (ref "C14") (pin "2") (pinfunction "2_2") (pintype "passive"))
      (node (ref "C16") (pin "2") (pinfunction "2_2") (pintype "passive"))
      (node (ref "C17") (pin "2") (pinfunction "2_2") (pintype "passive"))
      (node (ref "C18") (pin "2") (pinfunction "2_2") (pintype "passive"))
      (node (ref "C19") (pin "2") (pinfunction "2_2") (pintype "passive"))
      (node (ref "C2") (pin "1") (pinfunction "1_1") (pintype "passive"))
      (node (ref "C20") (pin "2") (pinfunction "2_2") (pintype "passive"))
      (node (ref "C21") (pin "2") (pinfunction "2_2") (pintype "passive"))
      (node (ref "C22") (pin "2") (pinfunction "2_2") (pintype "passive"))
      (node (ref "C3") (pin "1") (pinfunction "1_1") (pintype "passive"))
      (node (ref "C4") (pin "1") (pinfunction "1_1") (pintype "passive"))
      (node (ref "C5") (pin "2") (pinfunction "2_2") (pintype "passive"))
      (node (ref "C6") (pin "2") (pinfunction "2_2") (pintype "passive"))
      (node (ref "C7") (pin "1") (pinfunction "1_1") (pintype "passive"))
      (node (ref "C8") (pin "2") (pinfunction "2_2") (pintype "passive"))
      (node (ref "C9") (pin "2") (pinfunction "2_2") (pintype "passive"))
      (node (ref "DC1") (pin "2") (pinfunction "2_2") (pintype "passive"))
      (node (ref "DC1") (pin "3") (pinfunction "3_3") (pintype "passive"))
      (node (ref "H2") (pin "2") (pinfunction "2_2") (pintype "passive"))
      (node (ref "H2") (pin "24") (pinfunction "24_24") (pintype "passive"))
      (node (ref "H2") (pin "28") (pinfunction "28_28") (pintype "passive"))
      (node (ref "H2") (pin "29") (pinfunction "29_29") (pintype "passive"))
      (node (ref "H4") (pin "9") (pinfunction "9_9") (pintype "passive"))
      (node (ref "J1") (pin "2") (pinfunction "2_2") (pintype "passive"))
      (node (ref "LED2") (pin "2") (pinfunction "C_2") (pintype "passive"))
      (node (ref "P3") (pin "4") (pinfunction "4_4") (pintype "passive"))
      (node (ref "P3") (pin "5") (pinfunction "5_5") (pintype "passive"))
      (node (ref "SW1") (pin "4") (pinfunction "4_4") (pintype "passive"))
      (node (ref "SW2") (pin "3") (pinfunction "3_3") (pintype "passive"))
      (node (ref "SW2") (pin "4") (pinfunction "4_4") (pintype "passive"))
      (node (ref "SW6") (pin "1") (pinfunction "1_1") (pintype "passive"))
      (node (ref "U2") (pin "2") (pinfunction "GND_2") (pintype "passive"))
      (node (ref "U3") (pin "1") (pinfunction "GND_1") (pintype "passive"))
      (node (ref "U4") (pin "3") (pinfunction "GND_3") (pintype "passive"))
      (node (ref "U6") (pin "1") (pinfunction "A0_1") (pintype "passive"))
      (node (ref "U6") (pin "2") (pinfunction "A1_2") (pintype "passive"))
      (node (ref "U6") (pin "3") (pinfunction "A2_3") (pintype "passive"))
      (node (ref "U6") (pin "4") (pinfunction "GND_4") (pintype "passive"))
      (node (ref "U6") (pin "7") (pinfunction "WP_7") (pintype "passive"))
      (node (ref "U7") (pin "4") (pinfunction "VSS_4") (pintype "passive"))
      (node (ref "U8") (pin "15") (pinfunction "VSS_15") (pintype "passive"))
      (node (ref "U8") (pin "31") (pinfunction "VSS_31") (pintype "passive"))
      (node (ref "U8") (pin "47") (pinfunction "VSS_47") (pintype "passive"))
      (node (ref "U8") (pin "63") (pinfunction "VSS_63") (pintype "passive"))
      (node (ref "USB1") (pin "1") (pinfunction "GND_1") (pintype "passive"))
      (node (ref "USB1") (pin "12") (pinfunction "GND_12") (pintype "passive"))
      (node (ref "USB1") (pin "13") (pinfunction "SHELL_13") (pintype "passive"))
      (node (ref "USB1") (pin "14") (pinfunction "SHELL_14") (pintype "passive"))
    )
    (net (code "63") (name "Net-(D1-A)") (class "Default")
      (node (ref "D1") (pin "2") (pinfunction "A_2") (pintype "passive"))
      (node (ref "DC1") (pin "1") (pinfunction "1_1") (pintype "passive"))
    )
    (net (code "64") (name "Net-(D2-A)") (class "Default")
      (node (ref "D2") (pin "2") (pinfunction "A_2") (pintype "passive"))
      (node (ref "R2") (pin "2") (pinfunction "2_2") (pintype "passive"))
    )
    (net (code "65") (name "Net-(LED1-A)") (class "Default")
      (node (ref "LED1") (pin "1") (pinfunction "A_1") (pintype "passive"))
      (node (ref "R4") (pin "2") (pinfunction "2_2") (pintype "passive"))
    )
    (net (code "66") (name "Net-(LED2-A)") (class "Default")
      (node (ref "LED2") (pin "1") (pinfunction "A_1") (pintype "passive"))
      (node (ref "R6") (pin "2") (pinfunction "2_2") (pintype "passive"))
    )
    (net (code "67") (name "Net-(U4-V3)") (class "Default")
      (node (ref "C7") (pin "2") (pinfunction "2_2") (pintype "passive"))
      (node (ref "U4") (pin "8") (pinfunction "V3_8") (pintype "passive"))
    )
    (net (code "68") (name "VBAT") (class "Default")
      (node (ref "D2") (pin "1") (pinfunction "C_1") (pintype "passive"))
      (node (ref "U8") (pin "1") (pinfunction "VBAT_1") (pintype "passive"))
    )
    (net (code "69") (name "VCC") (class "Default")
      (node (ref "C10") (pin "1") (pinfunction "1_1") (pintype "passive"))
      (node (ref "C11") (pin "1") (pinfunction "1_1") (pintype "passive"))
      (node (ref "C12") (pin "1") (pinfunction "1_1") (pintype "passive"))
      (node (ref "C13") (pin "1") (pinfunction "1_1") (pintype "passive"))
      (node (ref "C14") (pin "1") (pinfunction "1_1") (pintype "passive"))
      (node (ref "C9") (pin "1") (pinfunction "1_1") (pintype "passive"))
      (node (ref "J1") (pin "1") (pinfunction "1_1") (pintype "passive"))
      (node (ref "P3") (pin "1") (pinfunction "1_1") (pintype "passive"))
      (node (ref "R3") (pin "2") (pinfunction "2_2") (pintype "passive"))
      (node (ref "U8") (pin "16") (pinfunction "VDD_16") (pintype "passive"))
      (node (ref "U8") (pin "32") (pinfunction "VDD_32") (pintype "passive"))
      (node (ref "U8") (pin "48") (pinfunction "VDD_48") (pintype "passive"))
      (node (ref "U8") (pin "64") (pinfunction "VDD_64") (pintype "passive"))
    )
    (net (code "70") (name "VIN") (class "Default")
      (node (ref "C5") (pin "1") (pinfunction "1_1") (pintype "passive"))
      (node (ref "D1") (pin "1") (pinfunction "C_1") (pintype "passive"))
      (node (ref "P3") (pin "6") (pinfunction "6_6") (pintype "passive"))
      (node (ref "U2") (pin "1") (pinfunction "IN_1") (pintype "passive"))
    )
    (net (code "71") (name "unconnected-(H2-Pad34)") (class "Default")
      (node (ref "H2") (pin "34") (pinfunction "34_34") (pintype "passive+no_connect"))
    )
    (net (code "72") (name "unconnected-(H4-Pad2)") (class "Default")
      (node (ref "H4") (pin "2") (pinfunction "2_2") (pintype "passive+no_connect"))
    )
    (net (code "73") (name "unconnected-(H4-Pad3)") (class "Default")
      (node (ref "H4") (pin "3") (pinfunction "3_3") (pintype "passive+no_connect"))
    )
    (net (code "74") (name "unconnected-(H4-Pad4)") (class "Default")
      (node (ref "H4") (pin "4") (pinfunction "4_4") (pintype "passive+no_connect"))
    )
    (net (code "75") (name "unconnected-(H4-Pad6)") (class "Default")
      (node (ref "H4") (pin "6") (pinfunction "6_6") (pintype "passive+no_connect"))
    )
    (net (code "76") (name "unconnected-(H4-Pad8)") (class "Default")
      (node (ref "H4") (pin "8") (pinfunction "8_8") (pintype "passive+no_connect"))
    )
    (net (code "77") (name "unconnected-(H4-Pad10)") (class "Default")
      (node (ref "H4") (pin "10") (pinfunction "10_10") (pintype "passive+no_connect"))
    )
    (net (code "78") (name "unconnected-(SW1-Pad1)") (class "Default")
      (node (ref "SW1") (pin "1") (pinfunction "1_1") (pintype "passive+no_connect"))
    )
    (net (code "79") (name "unconnected-(SW1-Pad2)") (class "Default")
      (node (ref "SW1") (pin "2") (pinfunction "2_2") (pintype "passive+no_connect"))
    )
    (net (code "80") (name "unconnected-(SW1-Pad3)") (class "Default")
      (node (ref "SW1") (pin "3") (pinfunction "3_3") (pintype "passive+no_connect"))
    )
    (net (code "81") (name "unconnected-(SW6-Pad2)") (class "Default")
      (node (ref "SW6") (pin "2") (pinfunction "2_2") (pintype "passive+no_connect"))
    )
    (net (code "82") (name "unconnected-(SW6-Pad5)") (class "Default")
      (node (ref "SW6") (pin "5") (pinfunction "5_5") (pintype "passive+no_connect"))
    )
    (net (code "83") (name "unconnected-(SW6-Pad6)") (class "Default")
      (node (ref "SW6") (pin "6") (pinfunction "6_6") (pintype "passive+no_connect"))
    )
    (net (code "84") (name "unconnected-(U8-VDDA-Pad29)") (class "Default")
      (node (ref "U8") (pin "29") (pinfunction "VDDA_29") (pintype "passive"))
    )
    (net (code "85") (name "unconnected-(U8-VREF+-Pad28)") (class "Default")
      (node (ref "U8") (pin "28") (pinfunction "VREF+_28") (pintype "passive"))
    )
    (net (code "86") (name "unconnected-(U8-VSSA-Pad27)") (class "Default")
      (node (ref "U8") (pin "27") (pinfunction "VSSA_27") (pintype "passive"))
    )
    (net (code "87") (name "unconnected-(USB1-CC1-Pad4)") (class "Default")
      (node (ref "USB1") (pin "4") (pinfunction "CC1_4") (pintype "passive+no_connect"))
    )
    (net (code "88") (name "unconnected-(USB1-CC2-Pad10)") (class "Default")
      (node (ref "USB1") (pin "10") (pinfunction "CC2_10") (pintype "passive+no_connect"))
    )
    (net (code "89") (name "unconnected-(USB1-SBU1-Pad9)") (class "Default")
      (node (ref "USB1") (pin "9") (pinfunction "SBU1_9") (pintype "passive+no_connect"))
    )
    (net (code "90") (name "unconnected-(USB1-SBU2-Pad3)") (class "Default")
      (node (ref "USB1") (pin "3") (pinfunction "SBU2_3") (pintype "passive+no_connect"))
    )
  )
)
